# Motor-Supply-Section.net
KiCad netlist of a schematic drawn in Altium Designer
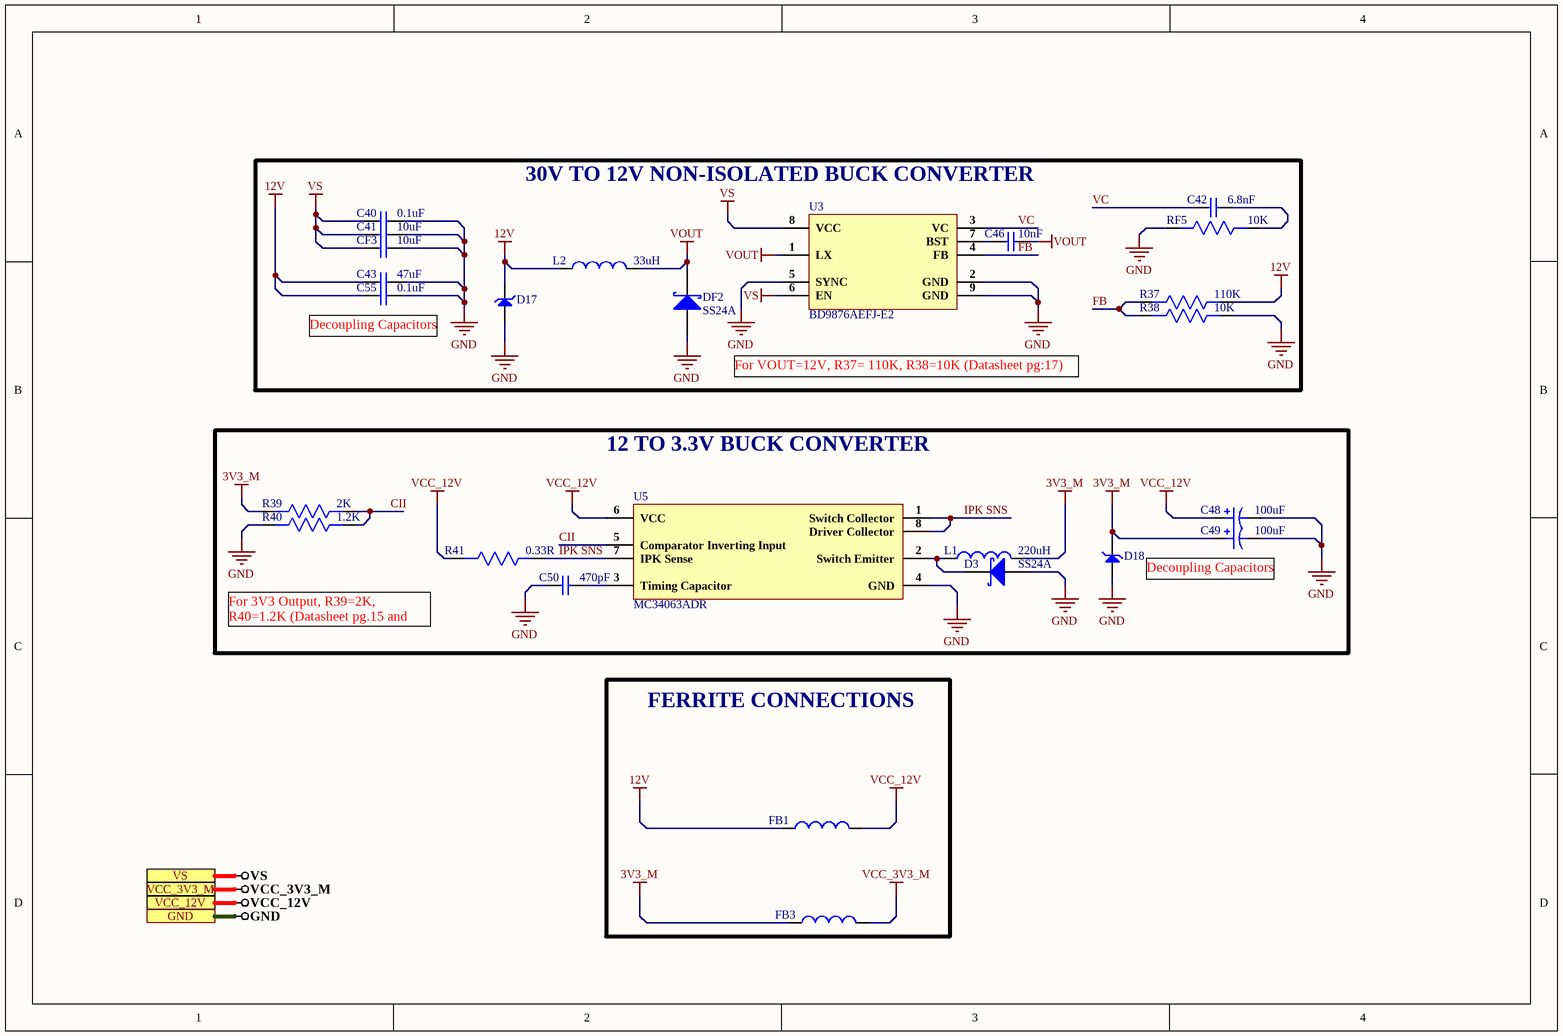
[diagram p0: Motor-Supply-Section.SchDoc]

(export (version "E")
  (design (tool "Eeschema 10.0.6"))
  (components
    (comp (ref "C40")
      (value "0.1uF")
      (footprint "Cap 0603")
      (description "Cap Ceramic 0.1uF 50VDC X7R 10% SMD 0603 Paper T/R")
      (fields
        (field (name "MANUFACTURER") "Samsung")
        (field (name "MANUFACTURER PART NUMBER") "CL10B104KB8NNNC")
      )
      (libsource (lib "Cole_Benson") (part "CL10B104KB8NNNC"))
    )
    (comp (ref "C41")
      (value "10uF")
      (footprint "Cap 0603")
      (description "10uF 35V X5R 20% Pad SMD 0603")
      (fields
        (field (name "MANUFACTURER") "Murata")
        (field (name "MANUFACTURER PART NUMBER") "GRM188R6YA106MA73D")
      )
      (libsource (lib "Cole_Benson") (part "GRM188R6YA106MA73D"))
    )
    (comp (ref "C42")
      (value "6.8nF")
      (footprint "Cap 0603")
      (description "50V 6.8nF X7R ±10% 0603")
      (fields (field (name "MANUFACTURER") "FH") (field (name "MANUFACTURER PART NUMBER") "0603B682K500NT"))
      (libsource (lib "Cole_Benson") (part "0603B682K500NT"))
    )
    (comp (ref "C43")
      (value "47uF")
      (footprint "Cap1206")
      (description "CAP CER 1206 47 uF 25 V ±20 % Tol. X5R")
      (fields
        (field (name "MANUFACTURER") "Murata")
        (field (name "MANUFACTURER PART NUMBER") "GRM31CR61E476ME44L")
      )
      (libsource (lib "Cole_Benson") (part "GRM31CR61E476ME44L"))
    )
    (comp (ref "C46")
      (value "10nF")
      (footprint "Cap 0402")
      (description "CAP CER 10000PF 25V X7R 0402")
      (fields
        (field (name "MANUFACTURER") "Yageo")
        (field (name "MANUFACTURER PART NUMBER") "CC0402KRX7R8BB103")
      )
      (libsource (lib "Cole_Benson") (part "CC0402KRX7R8BB103"))
    )
    (comp (ref "C48")
      (value "100uF")
      (footprint "CAP- 2917")
      (description "CAP TANT 100UF 20% 25V 2917")
      (fields
        (field (name "MANUFACTURER") "Kyocera AVX")
        (field (name "MANUFACTURER PART NUMBER") "TAJE107M025RNJ")
      )
      (libsource (lib "Cole_Benson") (part "TAJE107M025RNJ"))
    )
    (comp (ref "C49")
      (value "100uF")
      (footprint "CAP- 2917")
      (description "CAP TANT 100UF 20% 25V 2917")
      (fields
        (field (name "MANUFACTURER") "Kyocera AVX")
        (field (name "MANUFACTURER PART NUMBER") "TAJE107M025RNJ")
      )
      (libsource (lib "Cole_Benson") (part "TAJE107M025RNJ"))
    )
    (comp (ref "C50")
      (value "470pF")
      (footprint "Cap 0603")
      (description "CAP CER 470pF 10% X7R 50V 0603 SMD")
      (fields
        (field (name "MANUFACTURER") "Yageo")
        (field (name "MANUFACTURER PART NUMBER") "CC0603KRX7R9BB471")
      )
      (libsource (lib "Cole_Benson") (part "CC0603KRX7R9BB471"))
    )
    (comp (ref "C55")
      (value "0.1uF")
      (footprint "Cap 0603")
      (description "Cap Ceramic 0.1uF 50VDC X7R 10% SMD 0603 Paper T/R")
      (fields
        (field (name "MANUFACTURER") "Samsung")
        (field (name "MANUFACTURER PART NUMBER") "CL10B104KB8NNNC")
      )
      (libsource (lib "Cole_Benson") (part "CL10B104KB8NNNC"))
    )
    (comp (ref "CF3")
      (value "10uF")
      (footprint "Cap 0603")
      (description "10uF 35V X5R 20% Pad SMD 0603")
      (fields
        (field (name "MANUFACTURER") "Murata")
        (field (name "MANUFACTURER PART NUMBER") "GRM188R6YA106MA73D")
      )
      (libsource (lib "Cole_Benson") (part "GRM188R6YA106MA73D"))
    )
    (comp (ref "D3")
      (value "SS24A")
      (footprint "SMA")
      (description "40V 500mV@2A 2A SMA(DO-214AC) Schottky Barrier Diodes (SBD) ROHS")
      (fields (field (name "MANUFACTURER") "Yangzhou"))
      (libsource (lib "Cole_Benson") (part "SS24A"))
    )
    (comp (ref "D17")
      (value "MSMP12A-M3/89A")
      (footprint "MicroSMP")
      (description "TVS DIODE 12VWM 19.9VC MICROSMP")
      (fields (field (name "LCSC PART NUMBER") "C1973858"))
      (libsource (lib "Cole_Benson") (part "MSMP12A-M3/89A"))
    )
    (comp (ref "D18")
      (value "MSP3V3HM3/89A")
      (footprint "MicroSMP")
      (description "TVS DIODE 3.3VWM 11.5VC MICROSMP")
      (fields (field (name "LCSC PART NUMBER") "C241899"))
      (libsource (lib "Cole_Benson") (part "MSP3V3HM3/89A"))
    )
    (comp (ref "DF2")
      (value "SS24A")
      (footprint "SMA")
      (description "40V 500mV@2A 2A SMA(DO-214AC) Schottky Barrier Diodes (SBD) ROHS")
      (fields (field (name "MANUFACTURER") "Yangzhou"))
      (libsource (lib "Cole_Benson") (part "SS24A"))
    )
    (comp (ref "FB1")
      (value "MPZ1608S121ATDH5")
      (footprint "MPZ1608S121ATDH5")
      (description "Ferrite Beads Multi-Layer 120Ohm 25% 100MHz 2A 45mOhm DCR 0603 Automotive T/R")
      (fields (field (name "MANUFACTURER") "TDK") (field (name "TOLERANCE") "25%"))
      (libsource (lib "Cole_Benson") (part "MPZ1608S121ATDH5"))
    )
    (comp (ref "FB3")
      (value "MPZ1608S121ATDH5")
      (footprint "MPZ1608S121ATDH5")
      (description "Ferrite Beads Multi-Layer 120Ohm 25% 100MHz 2A 45mOhm DCR 0603 Automotive T/R")
      (fields (field (name "MANUFACTURER") "TDK") (field (name "TOLERANCE") "25%"))
      (libsource (lib "Cole_Benson") (part "MPZ1608S121ATDH5"))
    )
    (comp (ref "L1")
      (value "220uH")
      (footprint "SLF12575T-221M1R3-PF")
      (description "Inductor Power Shielded Wirewound 220uH 20% 1KHz Ferrite 1.3A 310mOhm DCR Blister T/R")
      (fields
        (field (name "MANUFACTURER") "TDK")
        (field (name "MANUFACTURER PART NUMBER") "SLF12575T-221M1R3-PF")
      )
      (libsource (lib "Cole_Benson") (part "SLF12575T-221M1R3-PF"))
    )
    (comp (ref "L2")
      (value "33uH")
      (footprint "PNLS5020-330")
      (description "1A 33uH ±20% 356mΩ SMD,5x5x2mm Power Inductors ROHS")
      (fields (field (name "MANUFACTURER") "DMBJ") (field (name "MANUFACTURER PART NUMBER") "PNLS5020-330"))
      (libsource (lib "Cole_Benson") (part "PNLS5020-330"))
    )
    (comp (ref "R37")
      (value "110K")
      (footprint "Res0603")
      (description "110kΩ 0603 Chip Resistor - Surface Mount ROHS")
      (fields
        (field (name "MANUFACTURER") "UNI-ROYAL")
        (field (name "MANUFACTURER PART NUMBER") "0603WAD1103T5E")
      )
      (libsource (lib "Cole_Benson") (part "0603WAD1103T5E"))
    )
    (comp (ref "R38")
      (value "10K")
      (footprint "Res0603")
      (description "RES SMD 10K Ohm 1% 1/10W 0603")
      (fields
        (field (name "MANUFACTURER") "Yageo")
        (field (name "MANUFACTURER PART NUMBER") "RC0603FR-0710KL")
      )
      (libsource (lib "Cole_Benson") (part "RC0603FR-0710KL"))
    )
    (comp (ref "R39")
      (value "2K")
      (footprint "Res0603")
      (description "RES SMD 2K OHM 1% 1/10W 0603")
      (fields
        (field (name "MANUFACTURER") "Yageo")
        (field (name "MANUFACTURER PART NUMBER") "RC0603FR-072KL")
      )
      (libsource (lib "Cole_Benson") (part "RC0603FR-072KL"))
    )
    (comp (ref "R40")
      (value "1.2K")
      (footprint "Res0603")
      (fields
        (field (name "MANUFACTURER") "UNI-ROYAL")
        (field (name "MANUFACTURER PART NO") "0603WAF1201T5E")
      )
      (libsource (lib "Cole_Benson") (part "0603WAF1201T5E"))
    )
    (comp (ref "R41")
      (value "0.33R")
      (footprint "Res0603")
      (fields (field (name "MANUFACTURER") "RALEC") (field (name "MANUFACTURER PART NO") "RTT03R330FTP"))
      (libsource (lib "Cole_Benson") (part "RTT03R330FTP"))
    )
    (comp (ref "RF5")
      (value "10K")
      (footprint "Res0603")
      (description "RES SMD 10K Ohm 1% 1/10W 0603")
      (fields
        (field (name "MANUFACTURER") "Yageo")
        (field (name "MANUFACTURER PART NUMBER") "RC0603FR-0710KL")
      )
      (libsource (lib "Cole_Benson") (part "RC0603FR-0710KL"))
    )
    (comp (ref "U3")
      (value "BD9876AEFJ-E2")
      (footprint "8-HTSOP-J")
      (description "NO Step-down type 1 Step-down 1V~29.4V 7V~42V 3A 300kHz SOIC-8_EP_150mil DC-DC Converters ROHS")
      (fields (field (name "MANUFACTURER") "ROHM Semicon"))
      (libsource (lib "Cole_Benson") (part "BD9876AEFJ-E2"))
    )
    (comp (ref "U5")
      (value "MC34063ADR")
      (footprint "SOIC-8")
      (description "1.5-A boost, buck, inverting switching regulator, operation from 0°C to 70°C 8-SOIC 0 to 70")
      (fields (field (name "MANUFACTURER") "Texas Instruments"))
      (libsource (lib "Cole_Benson") (part "MC34063ADR"))
    )
  )
  (nets
    (net (code "1") (name "/CII") (class "Default")
      (node (ref "R39") (pin "1") (pintype "passive"))
      (node (ref "R40") (pin "1") (pintype "passive"))
      (node (ref "U5") (pin "5") (pinfunction "Comparator_Inverting_Input_5") (pintype "passive"))
    )
    (net (code "2") (name "/FB") (class "Default")
      (node (ref "R37") (pin "2") (pintype "passive"))
      (node (ref "R38") (pin "2") (pintype "passive"))
      (node (ref "U3") (pin "4") (pinfunction "FB_4") (pintype "passive"))
    )
    (net (code "3") (name "/IPK SNS") (class "Default")
      (node (ref "R41") (pin "1") (pintype "passive"))
      (node (ref "U5") (pin "1") (pinfunction "Switch_Collector_1") (pintype "passive"))
      (node (ref "U5") (pin "7") (pinfunction "IPK_Sense_7") (pintype "passive"))
      (node (ref "U5") (pin "8") (pinfunction "Driver_Collector_8") (pintype "passive"))
    )
    (net (code "4") (name "/VC") (class "Default")
      (node (ref "C42") (pin "1") (pinfunction "1_1") (pintype "passive"))
      (node (ref "U3") (pin "3") (pinfunction "VC_3") (pintype "passive"))
    )
    (net (code "5") (name "3V3_M") (class "Default")
      (node (ref "C49") (pin "1") (pinfunction "1_1") (pintype "passive"))
      (node (ref "D18") (pin "2") (pinfunction "K_2") (pintype "passive"))
      (node (ref "FB3") (pin "1") (pinfunction "1_1") (pintype "passive"))
      (node (ref "L1") (pin "2") (pinfunction "2_2") (pintype "passive"))
      (node (ref "R39") (pin "2") (pintype "passive"))
    )
    (net (code "6") (name "12V") (class "Default")
      (node (ref "C43") (pin "1") (pinfunction "1_1") (pintype "passive"))
      (node (ref "C55") (pin "1") (pinfunction "1_1") (pintype "passive"))
      (node (ref "D17") (pin "2") (pinfunction "K_2") (pintype "passive"))
      (node (ref "FB1") (pin "1") (pinfunction "1_1") (pintype "passive"))
      (node (ref "L2") (pin "1") (pinfunction "1_1") (pintype "passive"))
      (node (ref "R37") (pin "1") (pintype "passive"))
    )
    (net (code "7") (name "GND") (class "Default")
      (node (ref "C40") (pin "2") (pinfunction "2_2") (pintype "passive"))
      (node (ref "C41") (pin "2") (pinfunction "2_2") (pintype "passive"))
      (node (ref "C43") (pin "2") (pinfunction "2_2") (pintype "passive"))
      (node (ref "C48") (pin "2") (pinfunction "2_2") (pintype "passive"))
      (node (ref "C49") (pin "2") (pinfunction "2_2") (pintype "passive"))
      (node (ref "C50") (pin "1") (pinfunction "1_1") (pintype "passive"))
      (node (ref "C55") (pin "2") (pinfunction "2_2") (pintype "passive"))
      (node (ref "CF3") (pin "2") (pinfunction "2_2") (pintype "passive"))
      (node (ref "D17") (pin "1") (pinfunction "A_1") (pintype "passive"))
      (node (ref "D18") (pin "1") (pinfunction "A_1") (pintype "passive"))
      (node (ref "D3") (pin "2") (pinfunction "A_2") (pintype "passive"))
      (node (ref "DF2") (pin "2") (pinfunction "A_2") (pintype "passive"))
      (node (ref "R38") (pin "1") (pintype "passive"))
      (node (ref "R40") (pin "2") (pintype "passive"))
      (node (ref "RF5") (pin "2") (pintype "passive"))
      (node (ref "U3") (pin "2") (pinfunction "GND_2") (pintype "passive"))
      (node (ref "U3") (pin "5") (pinfunction "SYNC_5") (pintype "passive"))
      (node (ref "U3") (pin "9") (pinfunction "GND_9") (pintype "passive"))
      (node (ref "U5") (pin "4") (pinfunction "GND_4") (pintype "passive"))
    )
    (net (code "8") (name "Net-(C42-Pad2)") (class "Default")
      (node (ref "C42") (pin "2") (pinfunction "2_2") (pintype "passive"))
      (node (ref "RF5") (pin "1") (pintype "passive"))
    )
    (net (code "9") (name "Net-(D3-K)") (class "Default")
      (node (ref "D3") (pin "1") (pinfunction "K_1") (pintype "passive"))
      (node (ref "L1") (pin "1") (pinfunction "1_1") (pintype "passive"))
      (node (ref "U5") (pin "2") (pinfunction "Switch_Emitter_2") (pintype "passive"))
    )
    (net (code "10") (name "Net-(U3-BST)") (class "Default")
      (node (ref "C46") (pin "1") (pinfunction "1_1") (pintype "passive"))
      (node (ref "U3") (pin "7") (pinfunction "BST_7") (pintype "passive"))
    )
    (net (code "11") (name "Net-(U5-Timing_Capacitor)") (class "Default")
      (node (ref "C50") (pin "2") (pinfunction "2_2") (pintype "passive"))
      (node (ref "U5") (pin "3") (pinfunction "Timing_Capacitor_3") (pintype "passive"))
    )
    (net (code "12") (name "VCC_3V3_M") (class "Default")
      (node (ref "FB3") (pin "2") (pinfunction "2_2") (pintype "passive"))
    )
    (net (code "13") (name "VCC_12V") (class "Default")
      (node (ref "C48") (pin "1") (pinfunction "1_1") (pintype "passive"))
      (node (ref "FB1") (pin "2") (pinfunction "2_2") (pintype "passive"))
      (node (ref "R41") (pin "2") (pintype "passive"))
      (node (ref "U5") (pin "6") (pinfunction "VCC_6") (pintype "passive"))
    )
    (net (code "14") (name "VOUT") (class "Default")
      (node (ref "C46") (pin "2") (pinfunction "2_2") (pintype "passive"))
      (node (ref "DF2") (pin "1") (pinfunction "K_1") (pintype "passive"))
      (node (ref "L2") (pin "2") (pinfunction "2_2") (pintype "passive"))
      (node (ref "U3") (pin "1") (pinfunction "LX_1") (pintype "passive"))
    )
    (net (code "15") (name "VS") (class "Default")
      (node (ref "C40") (pin "1") (pinfunction "1_1") (pintype "passive"))
      (node (ref "C41") (pin "1") (pinfunction "1_1") (pintype "passive"))
      (node (ref "CF3") (pin "1") (pinfunction "1_1") (pintype "passive"))
      (node (ref "U3") (pin "6") (pinfunction "EN_6") (pintype "passive"))
      (node (ref "U3") (pin "8") (pinfunction "VCC_8") (pintype "passive"))
    )
  )
)
